# servoUSBrev0.net
KiCad netlist of a schematic drawn in Altium Designer
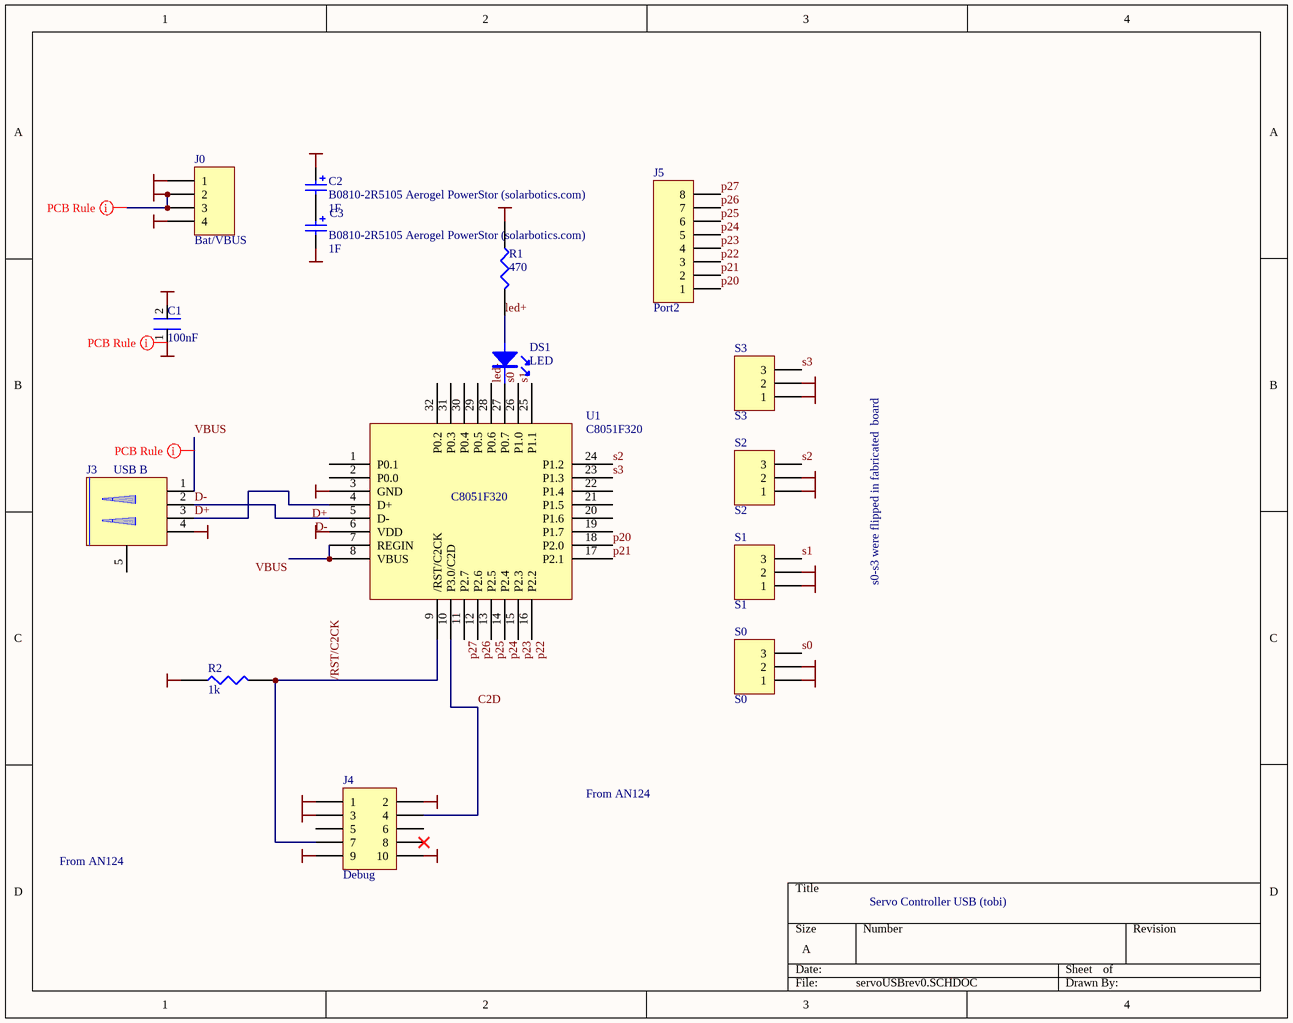
[diagram p0: servoUSBrev0.SCHDOC]

(export (version "E")
  (design (tool "Eeschema 10.0.6"))
  (components
    (comp (ref "C1")
      (value "100nF")
      (footprint "CC2013-0805")
      (libsource (lib "tobi SCHEMATIC") (part "CAPCHIP"))
    )
    (comp (ref "C2")
      (value "B0810-2R5105 Aerogel PowerStor (solarbotics.com)")
      (footprint "Capacitor - Electrolytic:CAPPR3.5-8X10.5")
      (description "Polarized Capacitor (Radial)")
      (fields (field (name "ALTIUM_VALUE") "1F") (field (name "PUBLISHER") "Altium Limited"))
      (libsource (lib "Miscellaneous Devices") (part "Cap Pol1"))
    )
    (comp (ref "C3")
      (value "B0810-2R5105 Aerogel PowerStor (solarbotics.com)")
      (footprint "Capacitor - Electrolytic:CAPPR3.5-8X10.5")
      (description "Polarized Capacitor (Radial)")
      (fields (field (name "ALTIUM_VALUE") "1F") (field (name "PUBLISHER") "Altium Limited"))
      (libsource (lib "Miscellaneous Devices") (part "Cap Pol1"))
    )
    (comp (ref "DS1")
      (value "LED")
      (footprint "0805LED")
      (description "LED, SMT 3mm by 1.5mm")
      (libsource (lib "SimpleMonitorUSBAER") (part "LED"))
    )
    (comp (ref "J0")
      (value "Bat/VBUS")
      (footprint "HDR1X4")
      (description "Header, 4-Pin")
      (fields (field (name "PUBLISHER") "Altium Limited"))
      (libsource (lib "Miscellaneous Connectors") (part "Header 4"))
    )
    (comp (ref "J3")
      (value "USB B")
      (footprint "usb")
      (description "USB TypB")
      (libsource (lib "DAC") (part "USB"))
    )
    (comp (ref "J4")
      (value "Debug")
      (footprint "HDR2X5")
      (description "Header, 5-Pin, Dual row")
      (fields (field (name "PUBLISHER") "Altium Limited"))
      (libsource (lib "Miscellaneous Connectors") (part "Header 5X2"))
    )
    (comp (ref "J5")
      (value "Port2")
      (footprint "HDR1X8")
      (description "Header, 8-Pin")
      (fields (field (name "PUBLISHER") "Altium Limited"))
      (libsource (lib "Miscellaneous Connectors") (part "Header 8"))
    )
    (comp (ref "R1") (value "470") (footprint "CR2012-0805") (libsource (lib "*") (part "RES1")))
    (comp (ref "R2") (value "1k") (footprint "CR2012-0805") (libsource (lib "*") (part "RES1")))
    (comp (ref "S0")
      (value "S0")
      (footprint "HDR1X3")
      (description "Header, 3-Pin")
      (fields (field (name "PUBLISHER") "Altium Limited"))
      (libsource (lib "Miscellaneous Connectors") (part "Header 3"))
    )
    (comp (ref "S1")
      (value "S1")
      (footprint "HDR1X3")
      (description "Header, 3-Pin")
      (fields (field (name "PUBLISHER") "Altium Limited"))
      (libsource (lib "Miscellaneous Connectors") (part "Header 3"))
    )
    (comp (ref "S2")
      (value "S2")
      (footprint "HDR1X3")
      (description "Header, 3-Pin")
      (fields (field (name "PUBLISHER") "Altium Limited"))
      (libsource (lib "Miscellaneous Connectors") (part "Header 3"))
    )
    (comp (ref "S3")
      (value "S3")
      (footprint "HDR1X3")
      (description "Header, 3-Pin")
      (fields (field (name "PUBLISHER") "Altium Limited"))
      (libsource (lib "Miscellaneous Connectors") (part "Header 3"))
    )
    (comp (ref "U1")
      (value "C8051F320")
      (footprint "TQFP32")
      (description "Silicon Labs USB Microcontroller")
      (libsource (lib "tobi SCHEMATIC") (part "C8051F320"))
    )
  )
  (nets
    (net (code "1") (name "/C2D") (class "Default")
      (node (ref "J4") (pin "4") (pinfunction "4_4") (pintype "passive"))
      (node (ref "U1") (pin "10") (pinfunction "P3.0/C2D_10") (pintype "passive"))
    )
    (net (code "2") (name "/D+") (class "Default")
      (node (ref "J3") (pin "3") (pintype "passive"))
      (node (ref "U1") (pin "4") (pinfunction "D+_4") (pintype "passive"))
    )
    (net (code "3") (name "/D-") (class "Default")
      (node (ref "J3") (pin "2") (pintype "passive"))
      (node (ref "U1") (pin "5") (pinfunction "D-_5") (pintype "passive"))
    )
    (net (code "4") (name "/led+") (class "Default")
      (node (ref "DS1") (pin "+") (pinfunction "1_+") (pintype "passive"))
      (node (ref "R1") (pin "2") (pinfunction "2_2") (pintype "passive"))
    )
    (net (code "5") (name "/led-") (class "Default")
      (node (ref "DS1") (pin "-") (pinfunction "2_-") (pintype "passive"))
      (node (ref "U1") (pin "27") (pinfunction "P0.7_27") (pintype "passive"))
    )
    (net (code "6") (name "/p20") (class "Default")
      (node (ref "J5") (pin "1") (pinfunction "1_1") (pintype "passive"))
      (node (ref "U1") (pin "18") (pinfunction "P2.0_18") (pintype "passive"))
    )
    (net (code "7") (name "/p21") (class "Default")
      (node (ref "J5") (pin "2") (pinfunction "2_2") (pintype "passive"))
      (node (ref "U1") (pin "17") (pinfunction "P2.1_17") (pintype "passive"))
    )
    (net (code "8") (name "/p22") (class "Default")
      (node (ref "J5") (pin "3") (pinfunction "3_3") (pintype "passive"))
      (node (ref "U1") (pin "16") (pinfunction "P2.2_16") (pintype "passive"))
    )
    (net (code "9") (name "/p23") (class "Default")
      (node (ref "J5") (pin "4") (pinfunction "4_4") (pintype "passive"))
      (node (ref "U1") (pin "15") (pinfunction "P2.3_15") (pintype "passive"))
    )
    (net (code "10") (name "/p24") (class "Default")
      (node (ref "J5") (pin "5") (pinfunction "5_5") (pintype "passive"))
      (node (ref "U1") (pin "14") (pinfunction "P2.4_14") (pintype "passive"))
    )
    (net (code "11") (name "/p25") (class "Default")
      (node (ref "J5") (pin "6") (pinfunction "6_6") (pintype "passive"))
      (node (ref "U1") (pin "13") (pinfunction "P2.5_13") (pintype "passive"))
    )
    (net (code "12") (name "/p26") (class "Default")
      (node (ref "J5") (pin "7") (pinfunction "7_7") (pintype "passive"))
      (node (ref "U1") (pin "12") (pinfunction "P2.6_12") (pintype "passive"))
    )
    (net (code "13") (name "/p27") (class "Default")
      (node (ref "J5") (pin "8") (pinfunction "8_8") (pintype "passive"))
      (node (ref "U1") (pin "11") (pinfunction "P2.7_11") (pintype "passive"))
    )
    (net (code "14") (name "/s0") (class "Default")
      (node (ref "S0") (pin "3") (pinfunction "3_3") (pintype "passive"))
      (node (ref "U1") (pin "26") (pinfunction "P1.0_26") (pintype "passive"))
    )
    (net (code "15") (name "/s1") (class "Default")
      (node (ref "S1") (pin "3") (pinfunction "3_3") (pintype "passive"))
      (node (ref "U1") (pin "25") (pinfunction "P1.1_25") (pintype "passive"))
    )
    (net (code "16") (name "/s2") (class "Default")
      (node (ref "S2") (pin "3") (pinfunction "3_3") (pintype "passive"))
      (node (ref "U1") (pin "24") (pinfunction "P1.2_24") (pintype "passive"))
    )
    (net (code "17") (name "/s3") (class "Default")
      (node (ref "S3") (pin "3") (pinfunction "3_3") (pintype "passive"))
      (node (ref "U1") (pin "23") (pinfunction "P1.3_23") (pintype "passive"))
    )
    (net (code "18") (name "/{slash}RST{slash}C2CK") (class "Default")
      (node (ref "J4") (pin "7") (pinfunction "7_7") (pintype "passive"))
      (node (ref "R2") (pin "2") (pinfunction "2_2") (pintype "passive"))
      (node (ref "U1") (pin "9") (pinfunction "/RST/C2CK_9") (pintype "passive"))
    )
    (net (code "19") (name "GND") (class "Default")
      (node (ref "C1") (pin "1") (pintype "passive"))
      (node (ref "C3") (pin "2") (pinfunction "2_2") (pintype "passive"))
      (node (ref "J0") (pin "1") (pinfunction "1_1") (pintype "passive"))
      (node (ref "J3") (pin "4") (pintype "passive"))
      (node (ref "J4") (pin "2") (pinfunction "2_2") (pintype "passive"))
      (node (ref "J4") (pin "3") (pinfunction "3_3") (pintype "passive"))
      (node (ref "J4") (pin "9") (pinfunction "9_9") (pintype "passive"))
      (node (ref "S0") (pin "1") (pinfunction "1_1") (pintype "passive"))
      (node (ref "S1") (pin "1") (pinfunction "1_1") (pintype "passive"))
      (node (ref "S2") (pin "1") (pinfunction "1_1") (pintype "passive"))
      (node (ref "S3") (pin "1") (pinfunction "1_1") (pintype "passive"))
      (node (ref "U1") (pin "3") (pinfunction "GND_3") (pintype "passive"))
    )
    (net (code "20") (name "Net-(C2-Pad2)") (class "Default")
      (node (ref "C2") (pin "2") (pinfunction "2_2") (pintype "passive"))
      (node (ref "C3") (pin "1") (pinfunction "1_1") (pintype "passive"))
    )
    (net (code "21") (name "SPOW") (class "Default")
      (node (ref "J0") (pin "2") (pinfunction "2_2") (pintype "passive"))
      (node (ref "J0") (pin "3") (pinfunction "3_3") (pintype "passive"))
      (node (ref "S0") (pin "2") (pinfunction "2_2") (pintype "passive"))
      (node (ref "S1") (pin "2") (pinfunction "2_2") (pintype "passive"))
      (node (ref "S2") (pin "2") (pinfunction "2_2") (pintype "passive"))
      (node (ref "S3") (pin "2") (pinfunction "2_2") (pintype "passive"))
    )
    (net (code "22") (name "VBUS") (class "Default")
      (node (ref "C2") (pin "1") (pinfunction "1_1") (pintype "passive"))
      (node (ref "J0") (pin "4") (pinfunction "4_4") (pintype "passive"))
      (node (ref "J3") (pin "1") (pintype "passive"))
      (node (ref "J4") (pin "10") (pinfunction "10_10") (pintype "passive"))
      (node (ref "U1") (pin "7") (pinfunction "REGIN_7") (pintype "passive"))
      (node (ref "U1") (pin "8") (pinfunction "VBUS_8") (pintype "passive"))
    )
    (net (code "23") (name "VDD") (class "Default")
      (node (ref "C1") (pin "2") (pintype "passive"))
      (node (ref "J4") (pin "1") (pinfunction "1_1") (pintype "passive"))
      (node (ref "R1") (pin "1") (pinfunction "1_1") (pintype "passive"))
      (node (ref "R2") (pin "1") (pinfunction "1_1") (pintype "passive"))
      (node (ref "U1") (pin "6") (pinfunction "VDD_6") (pintype "passive"))
    )
    (net (code "24") (name "unconnected-(J3-Pad5)") (class "Default")
      (node (ref "J3") (pin "5") (pintype "passive"))
    )
    (net (code "25") (name "unconnected-(J4-Pad5)") (class "Default")
      (node (ref "J4") (pin "5") (pinfunction "5_5") (pintype "passive"))
    )
    (net (code "26") (name "unconnected-(J4-Pad6)") (class "Default")
      (node (ref "J4") (pin "6") (pinfunction "6_6") (pintype "passive"))
    )
    (net (code "27") (name "unconnected-(J4-Pad8)") (class "Default")
      (node (ref "J4") (pin "8") (pinfunction "8_8") (pintype "passive+no_connect"))
    )
    (net (code "28") (name "unconnected-(U1-P0.0-Pad2)") (class "Default")
      (node (ref "U1") (pin "2") (pinfunction "P0.0_2") (pintype "passive"))
    )
    (net (code "29") (name "unconnected-(U1-P0.1-Pad1)") (class "Default")
      (node (ref "U1") (pin "1") (pinfunction "P0.1_1") (pintype "passive"))
    )
    (net (code "30") (name "unconnected-(U1-P0.2-Pad32)") (class "Default")
      (node (ref "U1") (pin "32") (pinfunction "P0.2_32") (pintype "passive"))
    )
    (net (code "31") (name "unconnected-(U1-P0.3-Pad31)") (class "Default")
      (node (ref "U1") (pin "31") (pinfunction "P0.3_31") (pintype "passive"))
    )
    (net (code "32") (name "unconnected-(U1-P0.4-Pad30)") (class "Default")
      (node (ref "U1") (pin "30") (pinfunction "P0.4_30") (pintype "passive"))
    )
    (net (code "33") (name "unconnected-(U1-P0.5-Pad29)") (class "Default")
      (node (ref "U1") (pin "29") (pinfunction "P0.5_29") (pintype "passive"))
    )
    (net (code "34") (name "unconnected-(U1-P0.6-Pad28)") (class "Default")
      (node (ref "U1") (pin "28") (pinfunction "P0.6_28") (pintype "passive"))
    )
    (net (code "35") (name "unconnected-(U1-P1.4-Pad22)") (class "Default")
      (node (ref "U1") (pin "22") (pinfunction "P1.4_22") (pintype "passive"))
    )
    (net (code "36") (name "unconnected-(U1-P1.5-Pad21)") (class "Default")
      (node (ref "U1") (pin "21") (pinfunction "P1.5_21") (pintype "passive"))
    )
    (net (code "37") (name "unconnected-(U1-P1.6-Pad20)") (class "Default")
      (node (ref "U1") (pin "20") (pinfunction "P1.6_20") (pintype "passive"))
    )
    (net (code "38") (name "unconnected-(U1-P1.7-Pad19)") (class "Default")
      (node (ref "U1") (pin "19") (pinfunction "P1.7_19") (pintype "passive"))
    )
  )
)
